# Esp8266-01_PACSSol.net
KiCad netlist of a schematic drawn in EAGLE
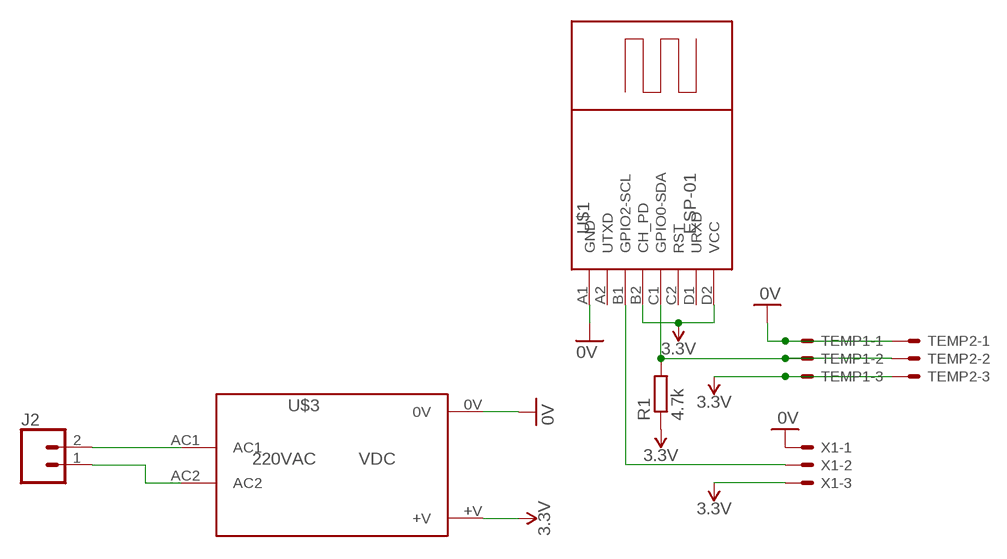
[diagram p0: schematic, sheet 1]

(export (version "E")
  (design (tool "Eeschema 10.0.6"))
  (components
    (comp (ref "J2")
      (value "CONN_025MM")
      (footprint "eagle-import:BORNIER_A_VIS_2_5.12MM")
      (libsource (lib "eagle-import") (part "CONN_025MM"))
    )
    (comp (ref "R1")
      (value "4.7k")
      (footprint "eagle-import:0207_10")
      (libsource (lib "eagle-import") (part "R-EU_0207/10"))
    )
    (comp (ref "TEMP1")
      (value "JST-XH-03-PIN-LONG-PAD")
      (footprint "eagle-import:JST-XH-03-PACKAGE-LONG-PAD")
      (libsource (lib "eagle-import") (part "JST-XH-03-PIN-LONG-PAD"))
    )
    (comp (ref "TEMP2")
      (value "JST-XH-03-PIN-LONG-PAD")
      (footprint "eagle-import:JST-XH-03-PACKAGE-LONG-PAD")
      (libsource (lib "eagle-import") (part "JST-XH-03-PIN-LONG-PAD"))
    )
    (comp (ref "U$1")
      (value "ESP-01")
      (footprint "eagle-import:ESP-01")
      (libsource (lib "eagle-import") (part "ESP-01"))
    )
    (comp (ref "U$3")
      (value "TSP05-5V-3W")
      (footprint "eagle-import:TSP05-VDC-3W")
      (libsource (lib "eagle-import") (part "TSP05-5V-3W"))
    )
    (comp (ref "X1")
      (value "JST-XH-03-PIN-LONG-PAD")
      (footprint "eagle-import:JST-XH-03-PACKAGE-LONG-PAD")
      (libsource (lib "eagle-import") (part "JST-XH-03-PIN-LONG-PAD"))
    )
  )
  (nets
    (net (code "1") (name "0V") (class "Default")
      (node (ref "TEMP1") (pin "1") (pinfunction "S_1") (pintype "passive"))
      (node (ref "TEMP2") (pin "1") (pinfunction "S_1") (pintype "passive"))
      (node (ref "U$1") (pin "A1") (pinfunction "GND_A1") (pintype "power_in"))
      (node (ref "U$3") (pin "0V") (pinfunction "0V_0V") (pintype "output"))
      (node (ref "X1") (pin "1") (pinfunction "S_1") (pintype "passive"))
    )
    (net (code "2") (name "3.3V") (class "Default")
      (node (ref "R1") (pin "1") (pinfunction "1_1") (pintype "passive"))
      (node (ref "TEMP1") (pin "3") (pinfunction "S_3") (pintype "passive"))
      (node (ref "TEMP2") (pin "3") (pinfunction "S_3") (pintype "passive"))
      (node (ref "U$1") (pin "B2") (pinfunction "CH_PD_B2") (pintype "bidirectional"))
      (node (ref "U$1") (pin "D2") (pinfunction "VCC_D2") (pintype "power_in"))
      (node (ref "U$3") (pin "+V") (pinfunction "+V_+V") (pintype "output"))
      (node (ref "X1") (pin "3") (pinfunction "S_3") (pintype "passive"))
    )
    (net (code "3") (name "Net-(J2-Pad1)") (class "Default")
      (node (ref "J2") (pin "1") (pinfunction "1_1") (pintype "passive"))
      (node (ref "U$3") (pin "AC2") (pinfunction "AC2_AC2") (pintype "input"))
    )
    (net (code "4") (name "Net-(J2-Pad2)") (class "Default")
      (node (ref "J2") (pin "2") (pinfunction "2_2") (pintype "passive"))
      (node (ref "U$3") (pin "AC1") (pinfunction "AC1_AC1") (pintype "bidirectional"))
    )
    (net (code "5") (name "Net-(TEMP1B-S)") (class "Default")
      (node (ref "R1") (pin "2") (pinfunction "2_2") (pintype "passive"))
      (node (ref "TEMP1") (pin "2") (pinfunction "S_2") (pintype "passive"))
      (node (ref "TEMP2") (pin "2") (pinfunction "S_2") (pintype "passive"))
      (node (ref "U$1") (pin "C1") (pinfunction "GPIO0-SDA_C1") (pintype "bidirectional"))
    )
    (net (code "6") (name "Net-(U$1-GPIO2-SCL)") (class "Default")
      (node (ref "U$1") (pin "B1") (pinfunction "GPIO2-SCL_B1") (pintype "bidirectional"))
      (node (ref "X1") (pin "2") (pinfunction "S_2") (pintype "passive"))
    )
    (net (code "7") (name "unconnected-(U$1-RST-PadC2)") (class "Default")
      (node (ref "U$1") (pin "C2") (pinfunction "RST_C2") (pintype "bidirectional"))
    )
    (net (code "8") (name "unconnected-(U$1-URXD-PadD1)") (class "Default")
      (node (ref "U$1") (pin "D1") (pinfunction "URXD_D1") (pintype "bidirectional"))
    )
    (net (code "9") (name "unconnected-(U$1-UTXD-PadA2)") (class "Default")
      (node (ref "U$1") (pin "A2") (pinfunction "UTXD_A2") (pintype "bidirectional"))
    )
  )
)
